# RS232_MAX3222EEWN.net
KiCad netlist of a schematic drawn in Altium Designer
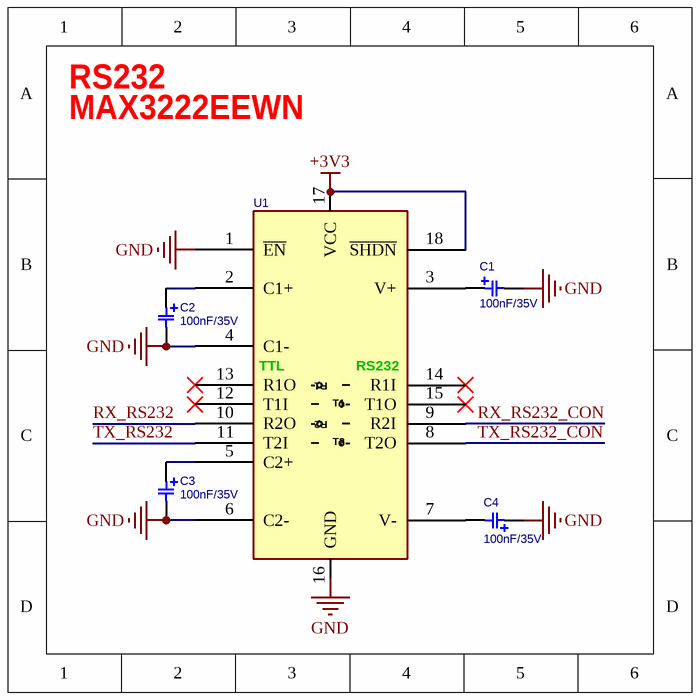
[diagram p0: RS232 MAX3222EEWN.SchDoc]

(export (version "E")
  (design (tool "Eeschema 10.0.6"))
  (components
    (comp (ref "C1")
      (value "100nF/35V")
      (footprint "C_TN_A")
      (description "CAP, SMD, TAN")
      (libsource (lib "PW Components 97_492") (part "CAP_SMD_TAN"))
    )
    (comp (ref "C2")
      (value "100nF/35V")
      (footprint "C_TN_A")
      (description "CAP, SMD, TAN")
      (libsource (lib "PW Components 97_492") (part "CAP_SMD_TAN"))
    )
    (comp (ref "C3")
      (value "100nF/35V")
      (footprint "C_TN_A")
      (description "CAP, SMD, TAN")
      (libsource (lib "PW Components 97_492") (part "CAP_SMD_TAN"))
    )
    (comp (ref "C4")
      (value "100nF/35V")
      (footprint "C_TN_A")
      (description "CAP, SMD, TAN")
      (libsource (lib "PW Components 97_492") (part "CAP_SMD_TAN"))
    )
    (comp (ref "U1")
      (value "~")
      (footprint "SO_18")
      (description "RS-232, DUAL, +3~5V, Driver/Receiver, Low-Power, up to 1Mbps, Using Four 0.1µF External Capacitor")
      (fields (field (name "MANF") "Maxim Integrated") (field (name "MANF_PART#") "MAX3232ECWE+"))
      (libsource (lib "PW Components 97_472") (part "RS232_MAX3222_SOP18W"))
    )
  )
  (nets
    (net (code "1") (name "+3V3") (class "Default")
      (node (ref "U1") (pin "17") (pinfunction "VCC_17") (pintype "power_in"))
      (node (ref "U1") (pin "18") (pinfunction "~{SHDN}_18") (pintype "passive"))
    )
    (net (code "2") (name "/RX_RS232") (class "Default")
      (node (ref "U1") (pin "10") (pinfunction "R2O_10") (pintype "passive"))
    )
    (net (code "3") (name "/RX_RS232_CON") (class "Default")
      (node (ref "U1") (pin "9") (pinfunction "R2I_9") (pintype "passive"))
    )
    (net (code "4") (name "/TX_RS232") (class "Default")
      (node (ref "U1") (pin "11") (pinfunction "T2I_11") (pintype "passive"))
    )
    (net (code "5") (name "/TX_RS232_CON") (class "Default")
      (node (ref "U1") (pin "8") (pinfunction "T2O_8") (pintype "passive"))
    )
    (net (code "6") (name "GND") (class "Default")
      (node (ref "C1") (pin "2") (pinfunction "2_2") (pintype "passive"))
      (node (ref "C2") (pin "2") (pinfunction "2_2") (pintype "passive"))
      (node (ref "C3") (pin "2") (pinfunction "2_2") (pintype "passive"))
      (node (ref "C4") (pin "1") (pinfunction "1_1") (pintype "passive"))
      (node (ref "U1") (pin "1") (pinfunction "~{EN}_1") (pintype "passive"))
      (node (ref "U1") (pin "16") (pinfunction "GND_16") (pintype "power_in"))
      (node (ref "U1") (pin "4") (pinfunction "C1-_4") (pintype "passive"))
      (node (ref "U1") (pin "6") (pinfunction "C2-_6") (pintype "passive"))
    )
    (net (code "7") (name "Net-(U1-C1+)") (class "Default")
      (node (ref "C2") (pin "1") (pinfunction "1_1") (pintype "passive"))
      (node (ref "U1") (pin "2") (pinfunction "C1+_2") (pintype "passive"))
    )
    (net (code "8") (name "Net-(U1-C2+)") (class "Default")
      (node (ref "C3") (pin "1") (pinfunction "1_1") (pintype "passive"))
      (node (ref "U1") (pin "5") (pinfunction "C2+_5") (pintype "passive"))
    )
    (net (code "9") (name "Net-(U1-V+)") (class "Default")
      (node (ref "C1") (pin "1") (pinfunction "1_1") (pintype "passive"))
      (node (ref "U1") (pin "3") (pinfunction "V+_3") (pintype "passive"))
    )
    (net (code "10") (name "Net-(U1-V-)") (class "Default")
      (node (ref "C4") (pin "2") (pinfunction "2_2") (pintype "passive"))
      (node (ref "U1") (pin "7") (pinfunction "V-_7") (pintype "passive"))
    )
    (net (code "11") (name "unconnected-(U1-R1I-Pad14)") (class "Default")
      (node (ref "U1") (pin "14") (pinfunction "R1I_14") (pintype "passive+no_connect"))
    )
    (net (code "12") (name "unconnected-(U1-R1O-Pad13)") (class "Default")
      (node (ref "U1") (pin "13") (pinfunction "R1O_13") (pintype "passive+no_connect"))
    )
    (net (code "13") (name "unconnected-(U1-T1I-Pad12)") (class "Default")
      (node (ref "U1") (pin "12") (pinfunction "T1I_12") (pintype "passive+no_connect"))
    )
    (net (code "14") (name "unconnected-(U1-T1O-Pad15)") (class "Default")
      (node (ref "U1") (pin "15") (pinfunction "T1O_15") (pintype "passive+no_connect"))
    )
  )
)
